# LNInterface.net
KiCad netlist of a schematic drawn in EAGLE
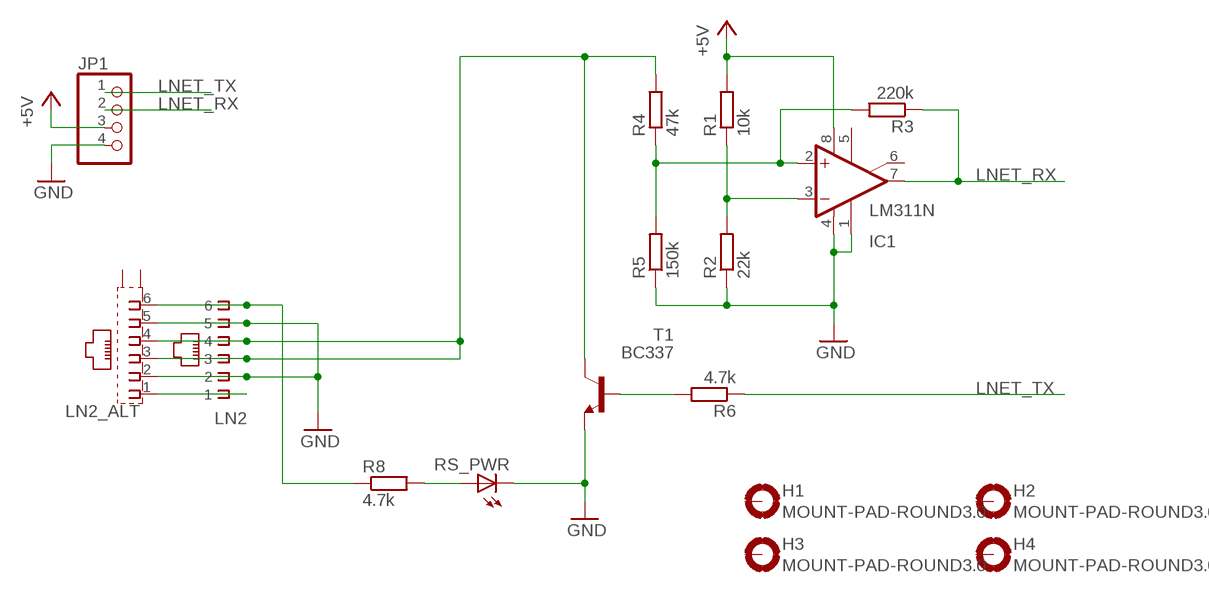
[diagram p0: schematic, sheet 1]

(export (version "E")
  (design (tool "Eeschema 10.0.6"))
  (components
    (comp (ref "H1")
      (value "MOUNT-PAD-ROUND3.0")
      (footprint "eagle-import:3,0-PAD")
      (libsource (lib "eagle-import") (part "MOUNT-PAD-ROUND3.0"))
    )
    (comp (ref "H2")
      (value "MOUNT-PAD-ROUND3.0")
      (footprint "eagle-import:3,0-PAD")
      (libsource (lib "eagle-import") (part "MOUNT-PAD-ROUND3.0"))
    )
    (comp (ref "H3")
      (value "MOUNT-PAD-ROUND3.0")
      (footprint "eagle-import:3,0-PAD")
      (libsource (lib "eagle-import") (part "MOUNT-PAD-ROUND3.0"))
    )
    (comp (ref "H4")
      (value "MOUNT-PAD-ROUND3.0")
      (footprint "eagle-import:3,0-PAD")
      (libsource (lib "eagle-import") (part "MOUNT-PAD-ROUND3.0"))
    )
    (comp (ref "IC1")
      (value "LM311N")
      (footprint "eagle-import:DIL08")
      (libsource (lib "eagle-import") (part "LM311N"))
    )
    (comp (ref "JP1")
      (value "PINHD-1X4")
      (footprint "eagle-import:1X04")
      (libsource (lib "eagle-import") (part "PINHD-1X4"))
    )
    (comp (ref "LN2")
      (value "RJ11-6X")
      (footprint "eagle-import:RJ11-NO_SHIELD")
      (libsource (lib "eagle-import") (part "RJ11-6X"))
    )
    (comp (ref "LN2_ALT")
      (value "YH-55-10")
      (footprint "eagle-import:YH-55-10")
      (libsource (lib "eagle-import") (part "YH-55-10"))
    )
    (comp (ref "R1")
      (value "10k")
      (footprint "eagle-import:0207_2V")
      (libsource (lib "eagle-import") (part "R-EU_0207/2V"))
    )
    (comp (ref "R2")
      (value "22k")
      (footprint "eagle-import:0207_2V")
      (libsource (lib "eagle-import") (part "R-EU_0207/2V"))
    )
    (comp (ref "R3")
      (value "220k")
      (footprint "eagle-import:0207_2V")
      (libsource (lib "eagle-import") (part "R-EU_0207/2V"))
    )
    (comp (ref "R4")
      (value "47k")
      (footprint "eagle-import:0207_2V")
      (libsource (lib "eagle-import") (part "R-EU_0207/2V"))
    )
    (comp (ref "R5")
      (value "150k")
      (footprint "eagle-import:0207_2V")
      (libsource (lib "eagle-import") (part "R-EU_0207/2V"))
    )
    (comp (ref "R6")
      (value "4.7k")
      (footprint "eagle-import:0207_2V")
      (libsource (lib "eagle-import") (part "R-EU_0207/2V"))
    )
    (comp (ref "R8")
      (value "4.7k")
      (footprint "eagle-import:0207_2V")
      (libsource (lib "eagle-import") (part "R-EU_0207/2V"))
    )
    (comp (ref "RS_PWR")
      (value "LED3MM")
      (footprint "eagle-import:LED3MM")
      (libsource (lib "eagle-import") (part "LED3MM"))
    )
    (comp (ref "T1")
      (value "BC337")
      (footprint "eagle-import:TO92")
      (libsource (lib "eagle-import") (part "BC337"))
    )
  )
  (nets
    (net (code "1") (name "+5V") (class "Default")
      (node (ref "IC1") (pin "8") (pinfunction "V+_8") (pintype "power_in"))
      (node (ref "JP1") (pin "3") (pinfunction "3_3") (pintype "passive"))
      (node (ref "R1") (pin "2") (pinfunction "2_2") (pintype "passive"))
    )
    (net (code "2") (name "/LNET_RX") (class "Default")
      (node (ref "IC1") (pin "7") (pinfunction "OUT_7") (pintype "output"))
      (node (ref "JP1") (pin "2") (pinfunction "2_2") (pintype "passive"))
      (node (ref "R3") (pin "1") (pinfunction "1_1") (pintype "passive"))
    )
    (net (code "3") (name "/LNET_TX") (class "Default")
      (node (ref "JP1") (pin "1") (pinfunction "1_1") (pintype "passive"))
      (node (ref "R6") (pin "1") (pinfunction "1_1") (pintype "passive"))
    )
    (net (code "4") (name "GND") (class "Default")
      (node (ref "IC1") (pin "1") (pinfunction "GND_1") (pintype "passive"))
      (node (ref "IC1") (pin "4") (pinfunction "V-_4") (pintype "power_in"))
      (node (ref "JP1") (pin "4") (pinfunction "4_4") (pintype "passive"))
      (node (ref "LN2") (pin "2") (pinfunction "2_2") (pintype "passive"))
      (node (ref "LN2") (pin "5") (pinfunction "5_5") (pintype "passive"))
      (node (ref "LN2_ALT") (pin "2") (pinfunction "2_2") (pintype "passive"))
      (node (ref "LN2_ALT") (pin "5") (pinfunction "5_5") (pintype "passive"))
      (node (ref "R2") (pin "1") (pinfunction "1_1") (pintype "passive"))
      (node (ref "R5") (pin "1") (pinfunction "1_1") (pintype "passive"))
      (node (ref "RS_PWR") (pin "K") (pinfunction "C_K") (pintype "passive"))
      (node (ref "T1") (pin "1") (pinfunction "E_1") (pintype "passive"))
    )
    (net (code "5") (name "Net-(IC1-+IN)") (class "Default")
      (node (ref "IC1") (pin "2") (pinfunction "+IN_2") (pintype "input"))
      (node (ref "R3") (pin "2") (pinfunction "2_2") (pintype "passive"))
      (node (ref "R4") (pin "1") (pinfunction "1_1") (pintype "passive"))
      (node (ref "R5") (pin "2") (pinfunction "2_2") (pintype "passive"))
    )
    (net (code "6") (name "Net-(IC1--IN)") (class "Default")
      (node (ref "IC1") (pin "3") (pinfunction "-IN_3") (pintype "input"))
      (node (ref "R1") (pin "1") (pinfunction "1_1") (pintype "passive"))
      (node (ref "R2") (pin "2") (pinfunction "2_2") (pintype "passive"))
    )
    (net (code "7") (name "Net-(LN2-Pad1)") (class "Default")
      (node (ref "LN2") (pin "1") (pinfunction "1_1") (pintype "passive"))
      (node (ref "LN2_ALT") (pin "1") (pinfunction "1_1") (pintype "passive"))
    )
    (net (code "8") (name "Net-(LN2-Pad6)") (class "Default")
      (node (ref "LN2") (pin "6") (pinfunction "6_6") (pintype "passive"))
      (node (ref "LN2_ALT") (pin "6") (pinfunction "6_6") (pintype "passive"))
      (node (ref "R8") (pin "1") (pinfunction "1_1") (pintype "passive"))
    )
    (net (code "9") (name "Net-(R8-Pad2)") (class "Default")
      (node (ref "R8") (pin "2") (pinfunction "2_2") (pintype "passive"))
      (node (ref "RS_PWR") (pin "A") (pinfunction "A_A") (pintype "passive"))
    )
    (net (code "10") (name "Net-(T1-B)") (class "Default")
      (node (ref "R6") (pin "2") (pinfunction "2_2") (pintype "passive"))
      (node (ref "T1") (pin "2") (pinfunction "B_2") (pintype "passive"))
    )
    (net (code "11") (name "Net-(T1-C)") (class "Default")
      (node (ref "LN2") (pin "3") (pinfunction "3_3") (pintype "passive"))
      (node (ref "LN2") (pin "4") (pinfunction "4_4") (pintype "passive"))
      (node (ref "LN2_ALT") (pin "3") (pinfunction "3_3") (pintype "passive"))
      (node (ref "LN2_ALT") (pin "4") (pinfunction "4_4") (pintype "passive"))
      (node (ref "R4") (pin "2") (pinfunction "2_2") (pintype "passive"))
      (node (ref "T1") (pin "3") (pinfunction "C_3") (pintype "passive"))
    )
    (net (code "12") (name "unconnected-(H1-MOUNT-PadB3,0)") (class "Default")
      (node (ref "H1") (pin "B3,0") (pinfunction "MOUNT_B3,0") (pintype "passive"))
    )
    (net (code "13") (name "unconnected-(H2-MOUNT-PadB3,0)") (class "Default")
      (node (ref "H2") (pin "B3,0") (pinfunction "MOUNT_B3,0") (pintype "passive"))
    )
    (net (code "14") (name "unconnected-(H3-MOUNT-PadB3,0)") (class "Default")
      (node (ref "H3") (pin "B3,0") (pinfunction "MOUNT_B3,0") (pintype "passive"))
    )
    (net (code "15") (name "unconnected-(H4-MOUNT-PadB3,0)") (class "Default")
      (node (ref "H4") (pin "B3,0") (pinfunction "MOUNT_B3,0") (pintype "passive"))
    )
    (net (code "16") (name "unconnected-(IC1-ON-Pad5)") (class "Default")
      (node (ref "IC1") (pin "5") (pinfunction "ON_5") (pintype "passive"))
    )
    (net (code "17") (name "unconnected-(IC1-ON{slash}STR-Pad6)") (class "Default")
      (node (ref "IC1") (pin "6") (pinfunction "ON/STR_6") (pintype "passive"))
    )
    (net (code "18") (name "unconnected-(LN2_ALT-S-PadS1)") (class "Default")
      (node (ref "LN2_ALT") (pin "S1") (pinfunction "S_S1") (pintype "passive"))
    )
    (net (code "19") (name "unconnected-(LN2_ALT-S-PadS2)") (class "Default")
      (node (ref "LN2_ALT") (pin "S2") (pinfunction "S_S2") (pintype "passive"))
    )
  )
)
